# M0.net
KiCad netlist of a schematic drawn in Altium Designer
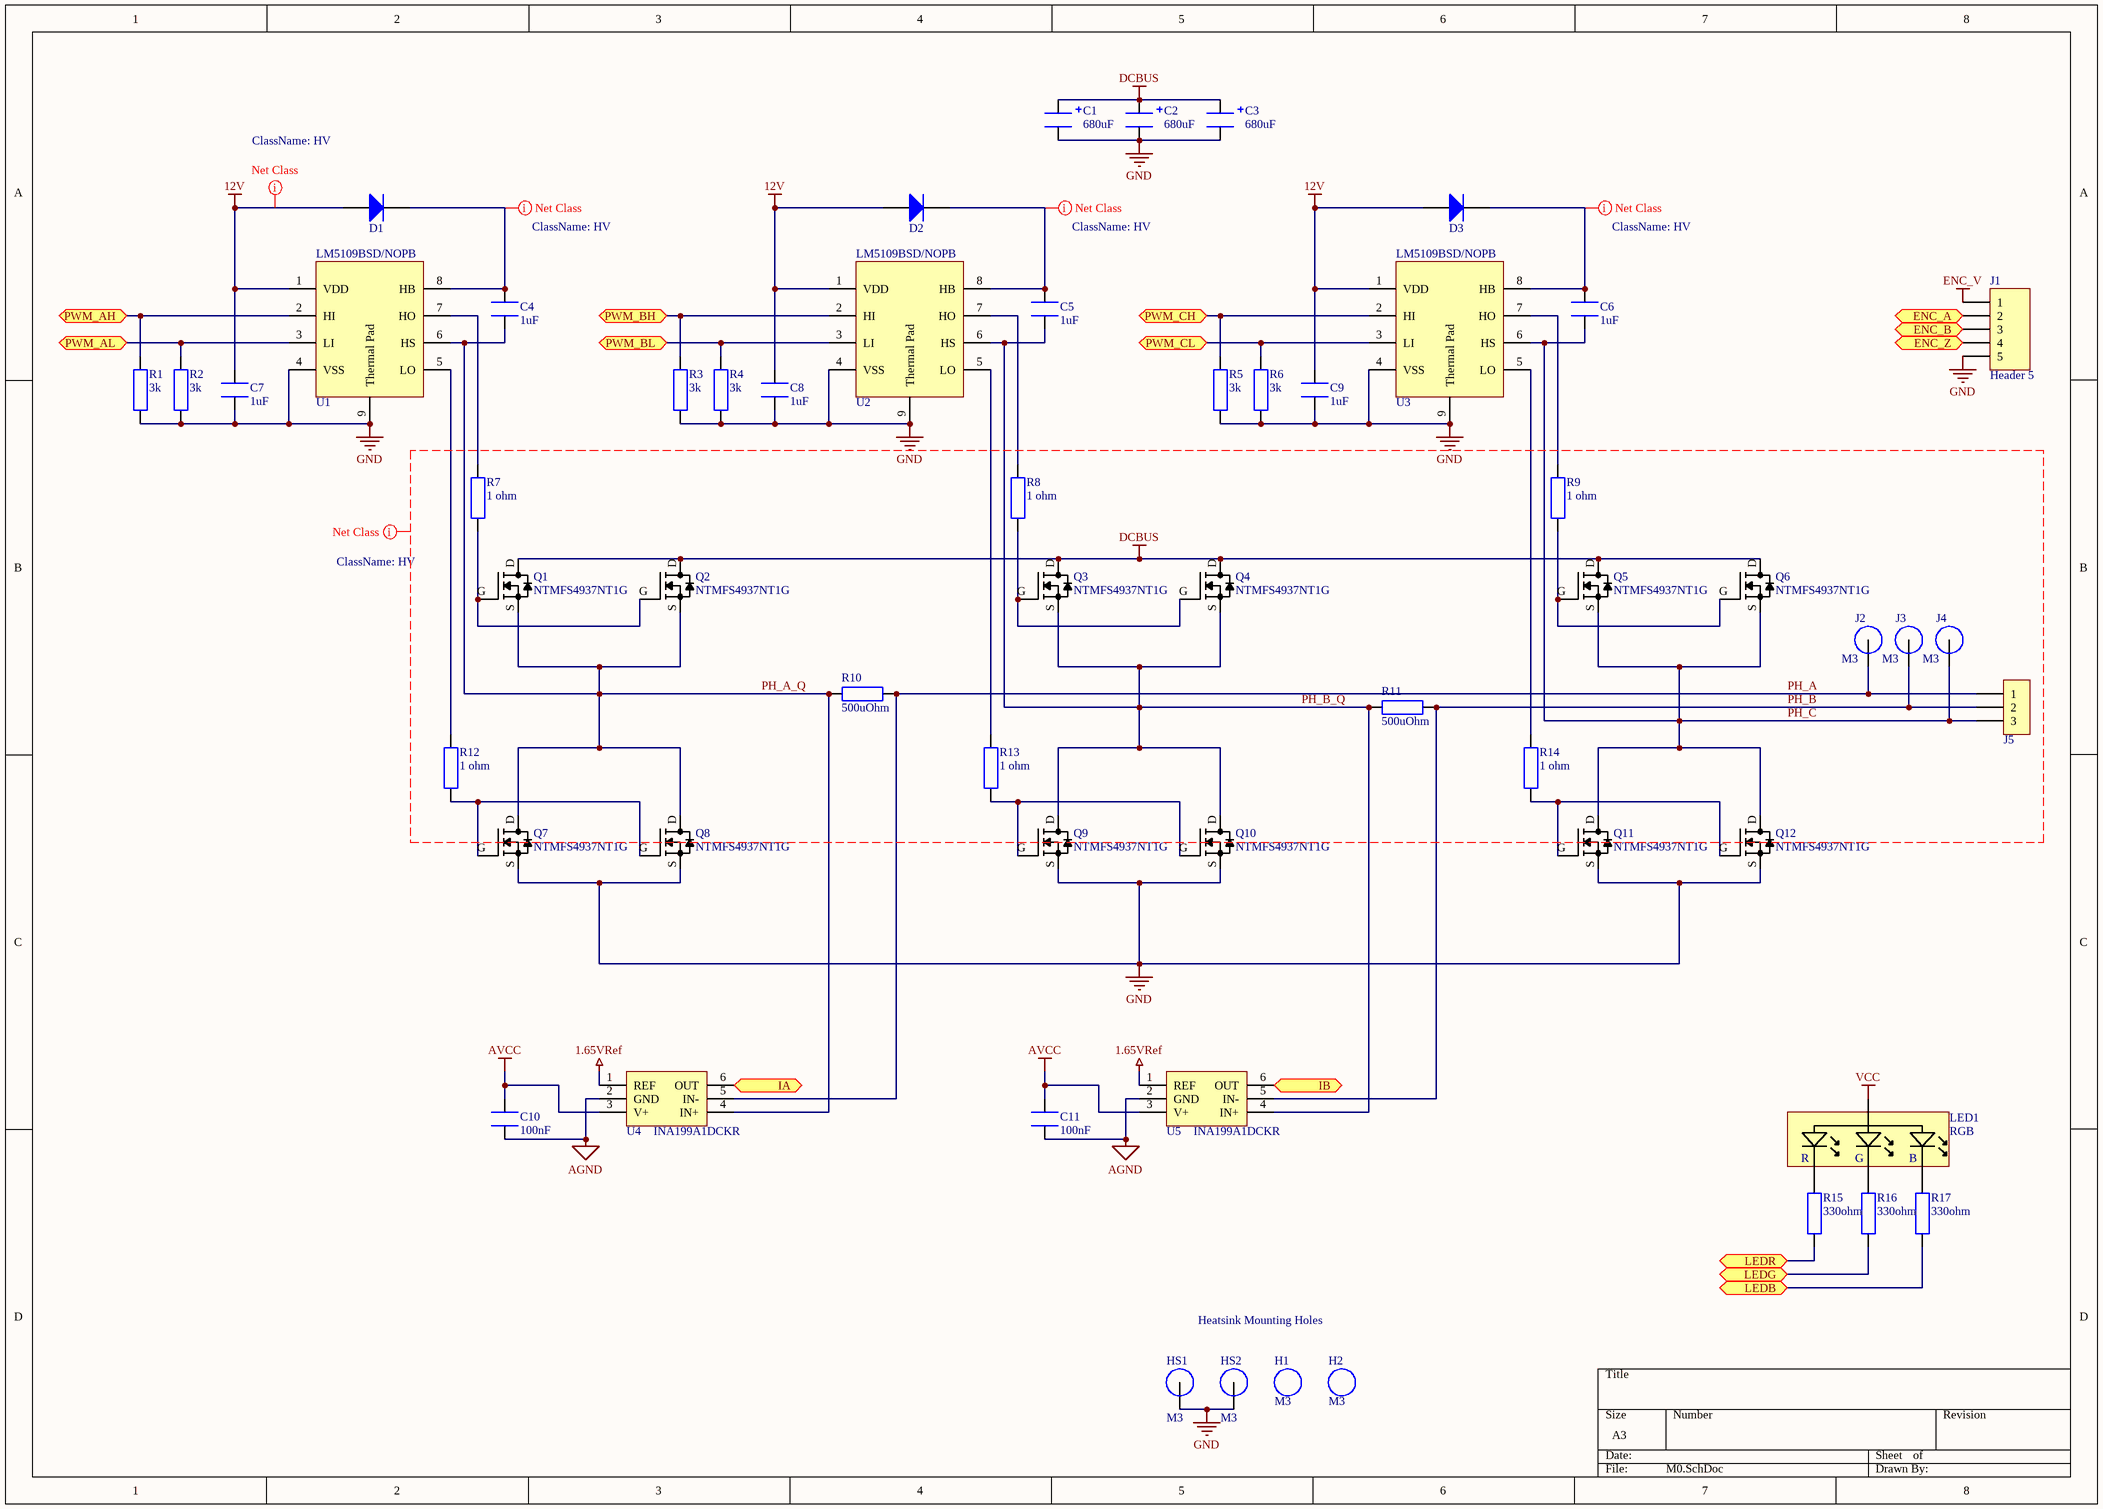
[diagram p0: M0.SchDoc]

(export (version "E")
  (design (tool "Eeschema 10.0.6"))
  (components
    (comp (ref "C1")
      (value "680uF")
      (footprint "CAPE10.0MM_Rad_10x14mm")
      (description "CAP, ALU ELEC, 680UF, 35V, RAD")
      (fields (field (name "Comment") "35ZLH680MEFC10X23"))
      (libsource (lib "CustomComponents") (part "35ZLH680MEFC10X23"))
    )
    (comp (ref "C2")
      (value "680uF")
      (footprint "CAPE10.0MM_Rad_10x14mm")
      (description "CAP, ALU ELEC, 680UF, 35V, RAD")
      (fields (field (name "Comment") "35ZLH680MEFC10X23"))
      (libsource (lib "CustomComponents") (part "35ZLH680MEFC10X23"))
    )
    (comp (ref "C3")
      (value "680uF")
      (footprint "CAPE10.0MM_Rad_10x14mm")
      (description "CAP, ALU ELEC, 680UF, 35V, RAD")
      (fields (field (name "Comment") "35ZLH680MEFC10X23"))
      (libsource (lib "CustomComponents") (part "35ZLH680MEFC10X23"))
    )
    (comp (ref "C4")
      (value "1uF")
      (footprint "1608[0603]")
      (description "CAP, MLCC, X5R, 1UF, 16V, 0603")
      (fields (field (name "Comment") "MC0603X105K160"))
      (libsource (lib "CustomComponents") (part "MC0603X105K160"))
    )
    (comp (ref "C5")
      (value "1uF")
      (footprint "1608[0603]")
      (description "CAP, MLCC, X5R, 1UF, 16V, 0603")
      (fields (field (name "Comment") "MC0603X105K160"))
      (libsource (lib "CustomComponents") (part "MC0603X105K160"))
    )
    (comp (ref "C6")
      (value "1uF")
      (footprint "1608[0603]")
      (description "CAP, MLCC, X5R, 1UF, 16V, 0603")
      (fields (field (name "Comment") "MC0603X105K160"))
      (libsource (lib "CustomComponents") (part "MC0603X105K160"))
    )
    (comp (ref "C7")
      (value "1uF")
      (footprint "1608[0603]")
      (description "CAP, MLCC, X5R, 1UF, 16V, 0603")
      (fields (field (name "Comment") "MC0603X105K160"))
      (libsource (lib "CustomComponents") (part "MC0603X105K160"))
    )
    (comp (ref "C8")
      (value "1uF")
      (footprint "1608[0603]")
      (description "CAP, MLCC, X5R, 1UF, 16V, 0603")
      (fields (field (name "Comment") "MC0603X105K160"))
      (libsource (lib "CustomComponents") (part "MC0603X105K160"))
    )
    (comp (ref "C9")
      (value "1uF")
      (footprint "1608[0603]")
      (description "CAP, MLCC, X5R, 1UF, 16V, 0603")
      (fields (field (name "Comment") "MC0603X105K160"))
      (libsource (lib "CustomComponents") (part "MC0603X105K160"))
    )
    (comp (ref "C10")
      (value "100nF")
      (footprint "1608[0603]")
      (description "CAP, MLCC, X7R, 100NF, 16V, 0603")
      (fields (field (name "Comment") "MC0603B104K160CT"))
      (libsource (lib "CustomComponents") (part "MC0603B104K160CT"))
    )
    (comp (ref "C11")
      (value "100nF")
      (footprint "1608[0603]")
      (description "CAP, MLCC, X7R, 100NF, 16V, 0603")
      (fields (field (name "Comment") "MC0603B104K160CT"))
      (libsource (lib "CustomComponents") (part "MC0603B104K160CT"))
    )
    (comp (ref "D1")
      (value "RB521S30T1G")
      (footprint "SOD523F")
      (description "DIODE, SCHOTTKY, 200MA, 30V")
      (libsource (lib "CustomComponents") (part "RB521S30T1G"))
    )
    (comp (ref "D2")
      (value "RB521S30T1G")
      (footprint "SOD523F")
      (description "DIODE, SCHOTTKY, 200MA, 30V")
      (libsource (lib "CustomComponents") (part "RB521S30T1G"))
    )
    (comp (ref "D3")
      (value "RB521S30T1G")
      (footprint "SOD523F")
      (description "DIODE, SCHOTTKY, 200MA, 30V")
      (libsource (lib "CustomComponents") (part "RB521S30T1G"))
    )
    (comp (ref "H1")
      (value "M3")
      (footprint "M3 Hole")
      (description "M3 Hole with no copper")
      (libsource (lib "CustomComponents") (part "M3 Hole"))
    )
    (comp (ref "H2")
      (value "M3")
      (footprint "M3 Hole")
      (description "M3 Hole with no copper")
      (libsource (lib "CustomComponents") (part "M3 Hole"))
    )
    (comp (ref "HS1")
      (value "M3")
      (footprint "M3 Mounting Hole")
      (description "M3 Mounting Hole")
      (libsource (lib "CustomComponents") (part "M3 Mounting Hole"))
    )
    (comp (ref "HS2")
      (value "M3")
      (footprint "M3 Mounting Hole")
      (description "M3 Mounting Hole")
      (libsource (lib "CustomComponents") (part "M3 Mounting Hole"))
    )
    (comp (ref "J1")
      (value "Header 5")
      (footprint "HDR1X5")
      (description "Header, 5-Pin")
      (fields (field (name "PUBLISHER") "Altium Limited"))
      (libsource (lib "Miscellaneous Connectors") (part "Header 5"))
    )
    (comp (ref "J2")
      (value "M3")
      (footprint "M3 Spade Hole")
      (description "M3 Spade Terminal")
      (libsource (lib "CustomComponents") (part "M3 Spade Terminal"))
    )
    (comp (ref "J3")
      (value "M3")
      (footprint "M3 Spade Hole")
      (description "M3 Spade Terminal")
      (libsource (lib "CustomComponents") (part "M3 Spade Terminal"))
    )
    (comp (ref "J4")
      (value "M3")
      (footprint "M3 Spade Hole")
      (description "M3 Spade Terminal")
      (libsource (lib "CustomComponents") (part "M3 Spade Terminal"))
    )
    (comp (ref "J5")
      (value "MC000051")
      (footprint "MC000051")
      (description "TERMINAL BLOCK, WIRE TO BRD, 3POS, 10AWG")
      (libsource (lib "CustomComponents") (part "MC000051"))
    )
    (comp (ref "LED1")
      (value "RGB")
      (footprint "ASMB-MTB1")
      (description "LED, HB, RGB, 0.09W, PLCC-4")
      (libsource (lib "CustomComponents") (part "ASMB-MTB1-0A3A2"))
    )
    (comp (ref "Q1")
      (value "NTMFS4937NT1G")
      (footprint "SO8FL_FILL")
      (description "MOSFET, N CH, 30V, 70A, SO-8 FL")
      (libsource (lib "CustomComponents") (part "NTMFS4937NT1G"))
    )
    (comp (ref "Q2")
      (value "NTMFS4937NT1G")
      (footprint "SO8FL_FILL")
      (description "MOSFET, N CH, 30V, 70A, SO-8 FL")
      (libsource (lib "CustomComponents") (part "NTMFS4937NT1G"))
    )
    (comp (ref "Q3")
      (value "NTMFS4937NT1G")
      (footprint "SO8FL_FILL")
      (description "MOSFET, N CH, 30V, 70A, SO-8 FL")
      (libsource (lib "CustomComponents") (part "NTMFS4937NT1G"))
    )
    (comp (ref "Q4")
      (value "NTMFS4937NT1G")
      (footprint "SO8FL_FILL")
      (description "MOSFET, N CH, 30V, 70A, SO-8 FL")
      (libsource (lib "CustomComponents") (part "NTMFS4937NT1G"))
    )
    (comp (ref "Q5")
      (value "NTMFS4937NT1G")
      (footprint "SO8FL_FILL")
      (description "MOSFET, N CH, 30V, 70A, SO-8 FL")
      (libsource (lib "CustomComponents") (part "NTMFS4937NT1G"))
    )
    (comp (ref "Q6")
      (value "NTMFS4937NT1G")
      (footprint "SO8FL_FILL")
      (description "MOSFET, N CH, 30V, 70A, SO-8 FL")
      (libsource (lib "CustomComponents") (part "NTMFS4937NT1G"))
    )
    (comp (ref "Q7")
      (value "NTMFS4937NT1G")
      (footprint "SO8FL_FILL")
      (description "MOSFET, N CH, 30V, 70A, SO-8 FL")
      (libsource (lib "CustomComponents") (part "NTMFS4937NT1G"))
    )
    (comp (ref "Q8")
      (value "NTMFS4937NT1G")
      (footprint "SO8FL_FILL")
      (description "MOSFET, N CH, 30V, 70A, SO-8 FL")
      (libsource (lib "CustomComponents") (part "NTMFS4937NT1G"))
    )
    (comp (ref "Q9")
      (value "NTMFS4937NT1G")
      (footprint "SO8FL_FILL")
      (description "MOSFET, N CH, 30V, 70A, SO-8 FL")
      (libsource (lib "CustomComponents") (part "NTMFS4937NT1G"))
    )
    (comp (ref "Q10")
      (value "NTMFS4937NT1G")
      (footprint "SO8FL_FILL")
      (description "MOSFET, N CH, 30V, 70A, SO-8 FL")
      (libsource (lib "CustomComponents") (part "NTMFS4937NT1G"))
    )
    (comp (ref "Q11")
      (value "NTMFS4937NT1G")
      (footprint "SO8FL_FILL")
      (description "MOSFET, N CH, 30V, 70A, SO-8 FL")
      (libsource (lib "CustomComponents") (part "NTMFS4937NT1G"))
    )
    (comp (ref "Q12")
      (value "NTMFS4937NT1G")
      (footprint "SO8FL_FILL")
      (description "MOSFET, N CH, 30V, 70A, SO-8 FL")
      (libsource (lib "CustomComponents") (part "NTMFS4937NT1G"))
    )
    (comp (ref "R1")
      (value "3k")
      (footprint "RESC1608X55N")
      (description "RESISTOR, 0603, 3K, 1%, ANTI SULFUR")
      (fields (field (name "Comment") "MCMR06X3001FTL"))
      (libsource (lib "CustomComponents") (part "MCMR06X3001FTL"))
    )
    (comp (ref "R2")
      (value "3k")
      (footprint "RESC1608X55N")
      (description "RESISTOR, 0603, 3K, 1%, ANTI SULFUR")
      (fields (field (name "Comment") "MCMR06X3001FTL"))
      (libsource (lib "CustomComponents") (part "MCMR06X3001FTL"))
    )
    (comp (ref "R3")
      (value "3k")
      (footprint "RESC1608X55N")
      (description "RESISTOR, 0603, 3K, 1%, ANTI SULFUR")
      (fields (field (name "Comment") "MCMR06X3001FTL"))
      (libsource (lib "CustomComponents") (part "MCMR06X3001FTL"))
    )
    (comp (ref "R4")
      (value "3k")
      (footprint "RESC1608X55N")
      (description "RESISTOR, 0603, 3K, 1%, ANTI SULFUR")
      (fields (field (name "Comment") "MCMR06X3001FTL"))
      (libsource (lib "CustomComponents") (part "MCMR06X3001FTL"))
    )
    (comp (ref "R5")
      (value "3k")
      (footprint "RESC1608X55N")
      (description "RESISTOR, 0603, 3K, 1%, ANTI SULFUR")
      (fields (field (name "Comment") "MCMR06X3001FTL"))
      (libsource (lib "CustomComponents") (part "MCMR06X3001FTL"))
    )
    (comp (ref "R6")
      (value "3k")
      (footprint "RESC1608X55N")
      (description "RESISTOR, 0603, 3K, 1%, ANTI SULFUR")
      (fields (field (name "Comment") "MCMR06X3001FTL"))
      (libsource (lib "CustomComponents") (part "MCMR06X3001FTL"))
    )
    (comp (ref "R7")
      (value "1 ohm")
      (footprint "RESC1608X55N")
      (description "RES, THICK FILM, 1OHM, 1%, 0.1W")
      (fields (field (name "Comment") "MCWR06W1R00FTL"))
      (libsource (lib "CustomComponents") (part "MCWR06W1R00FTL"))
    )
    (comp (ref "R8")
      (value "1 ohm")
      (footprint "RESC1608X55N")
      (description "RES, THICK FILM, 1OHM, 1%, 0.1W")
      (fields (field (name "Comment") "MCWR06W1R00FTL"))
      (libsource (lib "CustomComponents") (part "MCWR06W1R00FTL"))
    )
    (comp (ref "R9")
      (value "1 ohm")
      (footprint "RESC1608X55N")
      (description "RES, THICK FILM, 1OHM, 1%, 0.1W")
      (fields (field (name "Comment") "MCWR06W1R00FTL"))
      (libsource (lib "CustomComponents") (part "MCWR06W1R00FTL"))
    )
    (comp (ref "R10")
      (value "500uOhm")
      (footprint "RESC6332X70N")
      (description "RESISTOR, R0005, 2.0W, 1%")
      (fields (field (name "Comment") "TLR3A20DR0005FTDG"))
      (libsource (lib "CustomComponents") (part "TLR3A20DR0005FTDG"))
    )
    (comp (ref "R11")
      (value "500uOhm")
      (footprint "RESC6332X70N")
      (description "RESISTOR, R0005, 2.0W, 1%")
      (fields (field (name "Comment") "TLR3A20DR0005FTDG"))
      (libsource (lib "CustomComponents") (part "TLR3A20DR0005FTDG"))
    )
    (comp (ref "R12")
      (value "1 ohm")
      (footprint "RESC1608X55N")
      (description "RES, THICK FILM, 1OHM, 1%, 0.1W")
      (fields (field (name "Comment") "MCWR06W1R00FTL"))
      (libsource (lib "CustomComponents") (part "MCWR06W1R00FTL"))
    )
    (comp (ref "R13")
      (value "1 ohm")
      (footprint "RESC1608X55N")
      (description "RES, THICK FILM, 1OHM, 1%, 0.1W")
      (fields (field (name "Comment") "MCWR06W1R00FTL"))
      (libsource (lib "CustomComponents") (part "MCWR06W1R00FTL"))
    )
    (comp (ref "R14")
      (value "1 ohm")
      (footprint "RESC1608X55N")
      (description "RES, THICK FILM, 1OHM, 1%, 0.1W")
      (fields (field (name "Comment") "MCWR06W1R00FTL"))
      (libsource (lib "CustomComponents") (part "MCWR06W1R00FTL"))
    )
    (comp (ref "R15")
      (value "330ohm")
      (footprint "RESC1608X06L")
      (description "RES, THICK FILM, 330 OHM, 1%, 0.1W")
      (fields (field (name "Comment") "MCWR06X3300FTL"))
      (libsource (lib "CustomComponents") (part "MCWR06X3300FTL"))
    )
    (comp (ref "R16")
      (value "330ohm")
      (footprint "RESC1608X06L")
      (description "RES, THICK FILM, 330 OHM, 1%, 0.1W")
      (fields (field (name "Comment") "MCWR06X3300FTL"))
      (libsource (lib "CustomComponents") (part "MCWR06X3300FTL"))
    )
    (comp (ref "R17")
      (value "330ohm")
      (footprint "RESC1608X06L")
      (description "RES, THICK FILM, 330 OHM, 1%, 0.1W")
      (fields (field (name "Comment") "MCWR06X3300FTL"))
      (libsource (lib "CustomComponents") (part "MCWR06X3300FTL"))
    )
    (comp (ref "U1")
      (value "LM5109BSD/NOPB")
      (footprint "SON80P400X80_HS-9N")
      (description "DRIVER, MOSFET, HALF BRIDGE, WSON-8, 1A")
      (libsource (lib "CustomComponents") (part "LM5109BSD/NOPB"))
    )
    (comp (ref "U2")
      (value "LM5109BSD/NOPB")
      (footprint "SON80P400X80_HS-9N")
      (description "DRIVER, MOSFET, HALF BRIDGE, WSON-8, 1A")
      (libsource (lib "CustomComponents") (part "LM5109BSD/NOPB"))
    )
    (comp (ref "U3")
      (value "LM5109BSD/NOPB")
      (footprint "SON80P400X80_HS-9N")
      (description "DRIVER, MOSFET, HALF BRIDGE, WSON-8, 1A")
      (libsource (lib "CustomComponents") (part "LM5109BSD/NOPB"))
    )
    (comp (ref "U4")
      (value "INA199A1DCKR")
      (footprint "TSOP65P210X110-6N")
      (description "CURRENT SENSE AMP, 50V/V, 80KHZ")
      (libsource (lib "CustomComponents") (part "INA199A1DCKR"))
    )
    (comp (ref "U5")
      (value "INA199A1DCKR")
      (footprint "TSOP65P210X110-6N")
      (description "CURRENT SENSE AMP, 50V/V, 80KHZ")
      (libsource (lib "CustomComponents") (part "INA199A1DCKR"))
    )
  )
  (nets
    (net (code "1") (name "/ENC_A") (class "Default")
      (node (ref "J1") (pin "2") (pinfunction "2_2") (pintype "passive"))
    )
    (net (code "2") (name "/ENC_B") (class "Default")
      (node (ref "J1") (pin "3") (pinfunction "3_3") (pintype "passive"))
    )
    (net (code "3") (name "/ENC_Z") (class "Default")
      (node (ref "J1") (pin "4") (pinfunction "4_4") (pintype "passive"))
    )
    (net (code "4") (name "/IA") (class "Default")
      (node (ref "U4") (pin "6") (pinfunction "OUT_6") (pintype "passive"))
    )
    (net (code "5") (name "/IB") (class "Default")
      (node (ref "U5") (pin "6") (pinfunction "OUT_6") (pintype "passive"))
    )
    (net (code "6") (name "/LEDB") (class "Default")
      (node (ref "R17") (pin "2") (pinfunction "0_2") (pintype "passive"))
    )
    (net (code "7") (name "/LEDG") (class "Default")
      (node (ref "R16") (pin "2") (pinfunction "0_2") (pintype "passive"))
    )
    (net (code "8") (name "/LEDR") (class "Default")
      (node (ref "R15") (pin "2") (pinfunction "0_2") (pintype "passive"))
    )
    (net (code "9") (name "/PH_A") (class "Default")
      (node (ref "J2") (pin "1") (pinfunction "1_1") (pintype "passive"))
      (node (ref "J5") (pin "1") (pinfunction "1_1") (pintype "passive"))
      (node (ref "R10") (pin "1") (pinfunction "0_1") (pintype "passive"))
      (node (ref "U4") (pin "5") (pinfunction "IN-_5") (pintype "passive"))
    )
    (net (code "10") (name "/PH_A_Q") (class "Default")
      (node (ref "C4") (pin "1") (pinfunction "1_1") (pintype "passive"))
      (node (ref "Q1") (pin "S") (pinfunction "S_S") (pintype "passive"))
      (node (ref "Q2") (pin "S") (pinfunction "S_S") (pintype "passive"))
      (node (ref "Q7") (pin "D") (pinfunction "D_D") (pintype "passive"))
      (node (ref "Q8") (pin "D") (pinfunction "D_D") (pintype "passive"))
      (node (ref "R10") (pin "2") (pinfunction "0_2") (pintype "passive"))
      (node (ref "U1") (pin "6") (pinfunction "HS_6") (pintype "passive"))
      (node (ref "U4") (pin "4") (pinfunction "IN+_4") (pintype "passive"))
    )
    (net (code "11") (name "/PH_B") (class "Default")
      (node (ref "J3") (pin "1") (pinfunction "1_1") (pintype "passive"))
      (node (ref "J5") (pin "2") (pinfunction "2_2") (pintype "passive"))
      (node (ref "R11") (pin "1") (pinfunction "0_1") (pintype "passive"))
      (node (ref "U5") (pin "5") (pinfunction "IN-_5") (pintype "passive"))
    )
    (net (code "12") (name "/PH_B_Q") (class "Default")
      (node (ref "C5") (pin "1") (pinfunction "1_1") (pintype "passive"))
      (node (ref "Q10") (pin "D") (pinfunction "D_D") (pintype "passive"))
      (node (ref "Q3") (pin "S") (pinfunction "S_S") (pintype "passive"))
      (node (ref "Q4") (pin "S") (pinfunction "S_S") (pintype "passive"))
      (node (ref "Q9") (pin "D") (pinfunction "D_D") (pintype "passive"))
      (node (ref "R11") (pin "2") (pinfunction "0_2") (pintype "passive"))
      (node (ref "U2") (pin "6") (pinfunction "HS_6") (pintype "passive"))
      (node (ref "U5") (pin "4") (pinfunction "IN+_4") (pintype "passive"))
    )
    (net (code "13") (name "/PH_C") (class "Default")
      (node (ref "C6") (pin "1") (pinfunction "1_1") (pintype "passive"))
      (node (ref "J4") (pin "1") (pinfunction "1_1") (pintype "passive"))
      (node (ref "J5") (pin "3") (pinfunction "3_3") (pintype "passive"))
      (node (ref "Q11") (pin "D") (pinfunction "D_D") (pintype "passive"))
      (node (ref "Q12") (pin "D") (pinfunction "D_D") (pintype "passive"))
      (node (ref "Q5") (pin "S") (pinfunction "S_S") (pintype "passive"))
      (node (ref "Q6") (pin "S") (pinfunction "S_S") (pintype "passive"))
      (node (ref "U3") (pin "6") (pinfunction "HS_6") (pintype "passive"))
    )
    (net (code "14") (name "/PWM_AH") (class "Default")
      (node (ref "R1") (pin "2") (pinfunction "0_2") (pintype "passive"))
      (node (ref "U1") (pin "2") (pinfunction "HI_2") (pintype "passive"))
    )
    (net (code "15") (name "/PWM_AL") (class "Default")
      (node (ref "R2") (pin "2") (pinfunction "0_2") (pintype "passive"))
      (node (ref "U1") (pin "3") (pinfunction "LI_3") (pintype "passive"))
    )
    (net (code "16") (name "/PWM_BH") (class "Default")
      (node (ref "R3") (pin "2") (pinfunction "0_2") (pintype "passive"))
      (node (ref "U2") (pin "2") (pinfunction "HI_2") (pintype "passive"))
    )
    (net (code "17") (name "/PWM_BL") (class "Default")
      (node (ref "R4") (pin "2") (pinfunction "0_2") (pintype "passive"))
      (node (ref "U2") (pin "3") (pinfunction "LI_3") (pintype "passive"))
    )
    (net (code "18") (name "/PWM_CH") (class "Default")
      (node (ref "R5") (pin "2") (pinfunction "0_2") (pintype "passive"))
      (node (ref "U3") (pin "2") (pinfunction "HI_2") (pintype "passive"))
    )
    (net (code "19") (name "/PWM_CL") (class "Default")
      (node (ref "R6") (pin "2") (pinfunction "0_2") (pintype "passive"))
      (node (ref "U3") (pin "3") (pinfunction "LI_3") (pintype "passive"))
    )
    (net (code "20") (name "1.65VRef") (class "Default")
      (node (ref "U4") (pin "1") (pinfunction "REF_1") (pintype "passive"))
      (node (ref "U5") (pin "1") (pinfunction "REF_1") (pintype "passive"))
    )
    (net (code "21") (name "12V") (class "Default")
      (node (ref "C7") (pin "2") (pinfunction "2_2") (pintype "passive"))
      (node (ref "C8") (pin "2") (pinfunction "2_2") (pintype "passive"))
      (node (ref "C9") (pin "2") (pinfunction "2_2") (pintype "passive"))
      (node (ref "D1") (pin "A") (pinfunction "A_A") (pintype "passive"))
      (node (ref "D2") (pin "A") (pinfunction "A_A") (pintype "passive"))
      (node (ref "D3") (pin "A") (pinfunction "A_A") (pintype "passive"))
      (node (ref "U1") (pin "1") (pinfunction "VDD_1") (pintype "passive"))
      (node (ref "U2") (pin "1") (pinfunction "VDD_1") (pintype "passive"))
      (node (ref "U3") (pin "1") (pinfunction "VDD_1") (pintype "passive"))
    )
    (net (code "22") (name "AGND") (class "Default")
      (node (ref "C10") (pin "1") (pinfunction "1_1") (pintype "passive"))
      (node (ref "C11") (pin "1") (pinfunction "1_1") (pintype "passive"))
      (node (ref "U4") (pin "2") (pinfunction "GND_2") (pintype "passive"))
      (node (ref "U5") (pin "2") (pinfunction "GND_2") (pintype "passive"))
    )
    (net (code "23") (name "AVCC") (class "Default")
      (node (ref "C10") (pin "2") (pinfunction "2_2") (pintype "passive"))
      (node (ref "C11") (pin "2") (pinfunction "2_2") (pintype "passive"))
      (node (ref "U4") (pin "3") (pinfunction "V+_3") (pintype "passive"))
      (node (ref "U5") (pin "3") (pinfunction "V+_3") (pintype "passive"))
    )
    (net (code "24") (name "DCBUS") (class "Default")
      (node (ref "C1") (pin "1") (pinfunction "1_1") (pintype "passive"))
      (node (ref "C2") (pin "1") (pinfunction "1_1") (pintype "passive"))
      (node (ref "C3") (pin "1") (pinfunction "1_1") (pintype "passive"))
      (node (ref "Q1") (pin "D") (pinfunction "D_D") (pintype "passive"))
      (node (ref "Q2") (pin "D") (pinfunction "D_D") (pintype "passive"))
      (node (ref "Q3") (pin "D") (pinfunction "D_D") (pintype "passive"))
      (node (ref "Q4") (pin "D") (pinfunction "D_D") (pintype "passive"))
      (node (ref "Q5") (pin "D") (pinfunction "D_D") (pintype "passive"))
      (node (ref "Q6") (pin "D") (pinfunction "D_D") (pintype "passive"))
    )
    (net (code "25") (name "ENC_V") (class "Default")
      (node (ref "J1") (pin "1") (pinfunction "1_1") (pintype "passive"))
    )
    (net (code "26") (name "GND") (class "Default")
      (node (ref "C1") (pin "2") (pinfunction "2_2") (pintype "passive"))
      (node (ref "C2") (pin "2") (pinfunction "2_2") (pintype "passive"))
      (node (ref "C3") (pin "2") (pinfunction "2_2") (pintype "passive"))
      (node (ref "C7") (pin "1") (pinfunction "1_1") (pintype "passive"))
      (node (ref "C8") (pin "1") (pinfunction "1_1") (pintype "passive"))
      (node (ref "C9") (pin "1") (pinfunction "1_1") (pintype "passive"))
      (node (ref "HS1") (pin "1") (pinfunction "1_1") (pintype "passive"))
      (node (ref "HS2") (pin "1") (pinfunction "1_1") (pintype "passive"))
      (node (ref "J1") (pin "5") (pinfunction "5_5") (pintype "passive"))
      (node (ref "Q10") (pin "S") (pinfunction "S_S") (pintype "passive"))
      (node (ref "Q11") (pin "S") (pinfunction "S_S") (pintype "passive"))
      (node (ref "Q12") (pin "S") (pinfunction "S_S") (pintype "passive"))
      (node (ref "Q7") (pin "S") (pinfunction "S_S") (pintype "passive"))
      (node (ref "Q8") (pin "S") (pinfunction "S_S") (pintype "passive"))
      (node (ref "Q9") (pin "S") (pinfunction "S_S") (pintype "passive"))
      (node (ref "R1") (pin "1") (pinfunction "0_1") (pintype "passive"))
      (node (ref "R2") (pin "1") (pinfunction "0_1") (pintype "passive"))
      (node (ref "R3") (pin "1") (pinfunction "0_1") (pintype "passive"))
      (node (ref "R4") (pin "1") (pinfunction "0_1") (pintype "passive"))
      (node (ref "R5") (pin "1") (pinfunction "0_1") (pintype "passive"))
      (node (ref "R6") (pin "1") (pinfunction "0_1") (pintype "passive"))
      (node (ref "U1") (pin "4") (pinfunction "VSS_4") (pintype "passive"))
      (node (ref "U1") (pin "9") (pinfunction "Thermal_Pad_9") (pintype "passive"))
      (node (ref "U2") (pin "4") (pinfunction "VSS_4") (pintype "passive"))
      (node (ref "U2") (pin "9") (pinfunction "Thermal_Pad_9") (pintype "passive"))
      (node (ref "U3") (pin "4") (pinfunction "VSS_4") (pintype "passive"))
      (node (ref "U3") (pin "9") (pinfunction "Thermal_Pad_9") (pintype "passive"))
    )
    (net (code "27") (name "Net-(LED1-B)") (class "Default")
      (node (ref "LED1") (pin "3") (pinfunction "B_3") (pintype "passive"))
      (node (ref "R17") (pin "1") (pinfunction "0_1") (pintype "passive"))
    )
    (net (code "28") (name "Net-(LED1-G)") (class "Default")
      (node (ref "LED1") (pin "2") (pinfunction "G_2") (pintype "passive"))
      (node (ref "R16") (pin "1") (pinfunction "0_1") (pintype "passive"))
    )
    (net (code "29") (name "Net-(LED1-R)") (class "Default")
      (node (ref "LED1") (pin "1") (pinfunction "R_1") (pintype "passive"))
      (node (ref "R15") (pin "1") (pinfunction "0_1") (pintype "passive"))
    )
    (net (code "30") (name "Net-(Q1-PadG)") (class "Default")
      (node (ref "Q1") (pin "G") (pinfunction "G_G") (pintype "passive"))
      (node (ref "Q2") (pin "G") (pinfunction "G_G") (pintype "passive"))
      (node (ref "R7") (pin "1") (pinfunction "0_1") (pintype "passive"))
    )
    (net (code "31") (name "Net-(Q3-PadG)") (class "Default")
      (node (ref "Q3") (pin "G") (pinfunction "G_G") (pintype "passive"))
      (node (ref "Q4") (pin "G") (pinfunction "G_G") (pintype "passive"))
      (node (ref "R8") (pin "1") (pinfunction "0_1") (pintype "passive"))
    )
    (net (code "32") (name "Net-(Q5-PadG)") (class "Default")
      (node (ref "Q5") (pin "G") (pinfunction "G_G") (pintype "passive"))
      (node (ref "Q6") (pin "G") (pinfunction "G_G") (pintype "passive"))
      (node (ref "R9") (pin "1") (pinfunction "0_1") (pintype "passive"))
    )
    (net (code "33") (name "Net-(Q7-PadG)") (class "Default")
      (node (ref "Q7") (pin "G") (pinfunction "G_G") (pintype "passive"))
      (node (ref "Q8") (pin "G") (pinfunction "G_G") (pintype "passive"))
      (node (ref "R12") (pin "1") (pinfunction "0_1") (pintype "passive"))
    )
    (net (code "34") (name "Net-(Q10-PadG)") (class "Default")
      (node (ref "Q10") (pin "G") (pinfunction "G_G") (pintype "passive"))
      (node (ref "Q9") (pin "G") (pinfunction "G_G") (pintype "passive"))
      (node (ref "R13") (pin "1") (pinfunction "0_1") (pintype "passive"))
    )
    (net (code "35") (name "Net-(Q11-PadG)") (class "Default")
      (node (ref "Q11") (pin "G") (pinfunction "G_G") (pintype "passive"))
      (node (ref "Q12") (pin "G") (pinfunction "G_G") (pintype "passive"))
      (node (ref "R14") (pin "1") (pinfunction "0_1") (pintype "passive"))
    )
    (net (code "36") (name "Net-(U1-HB)") (class "Default")
      (node (ref "C4") (pin "2") (pinfunction "2_2") (pintype "passive"))
      (node (ref "D1") (pin "K") (pinfunction "K_K") (pintype "passive"))
      (node (ref "U1") (pin "8") (pinfunction "HB_8") (pintype "passive"))
    )
    (net (code "37") (name "Net-(U1-HO)") (class "Default")
      (node (ref "R7") (pin "2") (pinfunction "0_2") (pintype "passive"))
      (node (ref "U1") (pin "7") (pinfunction "HO_7") (pintype "passive"))
    )
    (net (code "38") (name "Net-(U1-LO)") (class "Default")
      (node (ref "R12") (pin "2") (pinfunction "0_2") (pintype "passive"))
      (node (ref "U1") (pin "5") (pinfunction "LO_5") (pintype "passive"))
    )
    (net (code "39") (name "Net-(U2-HB)") (class "Default")
      (node (ref "C5") (pin "2") (pinfunction "2_2") (pintype "passive"))
      (node (ref "D2") (pin "K") (pinfunction "K_K") (pintype "passive"))
      (node (ref "U2") (pin "8") (pinfunction "HB_8") (pintype "passive"))
    )
    (net (code "40") (name "Net-(U2-HO)") (class "Default")
      (node (ref "R8") (pin "2") (pinfunction "0_2") (pintype "passive"))
      (node (ref "U2") (pin "7") (pinfunction "HO_7") (pintype "passive"))
    )
    (net (code "41") (name "Net-(U2-LO)") (class "Default")
      (node (ref "R13") (pin "2") (pinfunction "0_2") (pintype "passive"))
      (node (ref "U2") (pin "5") (pinfunction "LO_5") (pintype "passive"))
    )
    (net (code "42") (name "Net-(U3-HB)") (class "Default")
      (node (ref "C6") (pin "2") (pinfunction "2_2") (pintype "passive"))
      (node (ref "D3") (pin "K") (pinfunction "K_K") (pintype "passive"))
      (node (ref "U3") (pin "8") (pinfunction "HB_8") (pintype "passive"))
    )
    (net (code "43") (name "Net-(U3-HO)") (class "Default")
      (node (ref "R9") (pin "2") (pinfunction "0_2") (pintype "passive"))
      (node (ref "U3") (pin "7") (pinfunction "HO_7") (pintype "passive"))
    )
    (net (code "44") (name "Net-(U3-LO)") (class "Default")
      (node (ref "R14") (pin "2") (pinfunction "0_2") (pintype "passive"))
      (node (ref "U3") (pin "5") (pinfunction "LO_5") (pintype "passive"))
    )
    (net (code "45") (name "VCC") (class "Default")
      (node (ref "LED1") (pin "4") (pinfunction "A_4") (pintype "passive"))
    )
  )
)
